# Filter.net
KiCad netlist of a schematic drawn in Altium Designer
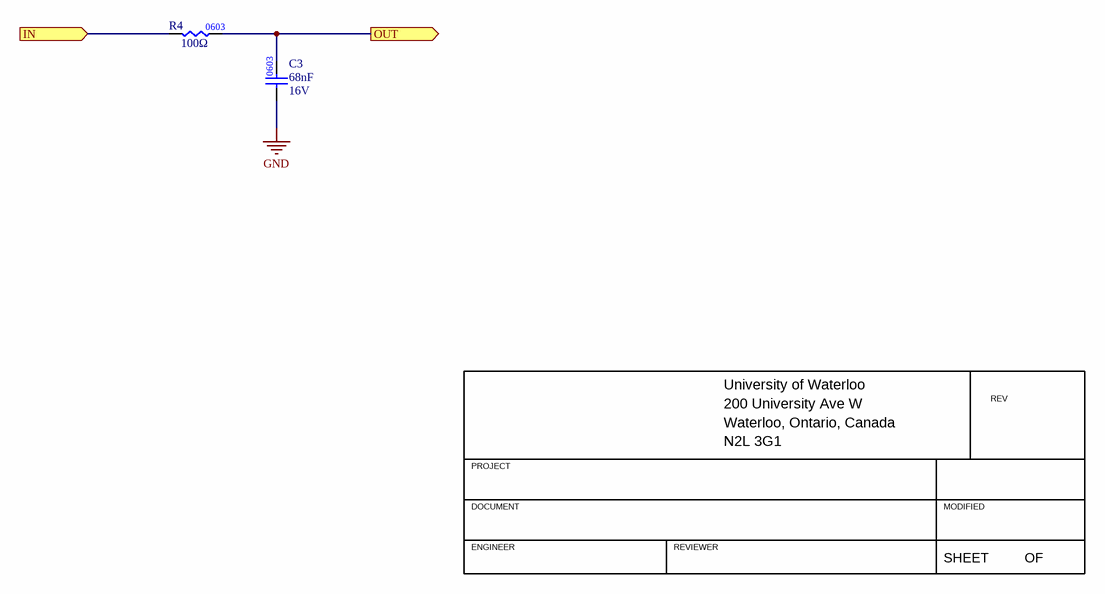
[diagram p0: Filter.SchDoc]

(export (version "E")
  (design (tool "Eeschema 10.0.6"))
  (components
    (comp (ref "C3")
      (value "CAP_0.068uF_16V_X7R_0603")
      (footprint "CAP0603")
      (description "CAP CER 0.068UF 16V X7R 0603")
      (fields
        (field (name "MANUFACTURER") "KYOCERA AVX")
        (field (name "MANUFACTURER PART NUMBER") "KGM15AR71C683KT")
        (field (name "CAPACITANCE") "68nF")
        (field (name "RATED DC VOLTAGE (URDC)") "16V")
      )
      (libsource (lib "Personal_Schematic_Library_2022") (part "CAP_0.068uF_16V_X7R_0603"))
    )
    (comp (ref "R4")
      (value "100Ω")
      (footprint "RES0603")
      (description "RES 100 OHM 1% 1/10W 0603")
      (fields (field (name "Comment") "RES_100Ω_0603_1%"))
      (libsource (lib "Personal_Schematic_Library_2022") (part "RES_100Ω_0603_1%"))
    )
  )
  (nets
    (net (code "1") (name "/IN") (class "Default")
      (node (ref "R4") (pin "1") (pinfunction "1_1") (pintype "passive"))
    )
    (net (code "2") (name "/OUT") (class "Default")
      (node (ref "C3") (pin "2") (pinfunction "2_2") (pintype "passive"))
      (node (ref "R4") (pin "2") (pinfunction "2_2") (pintype "passive"))
    )
    (net (code "3") (name "GND") (class "Default")
      (node (ref "C3") (pin "1") (pinfunction "1_1") (pintype "passive"))
    )
  )
)
